# Main.net
KiCad netlist of a schematic drawn in EAGLE
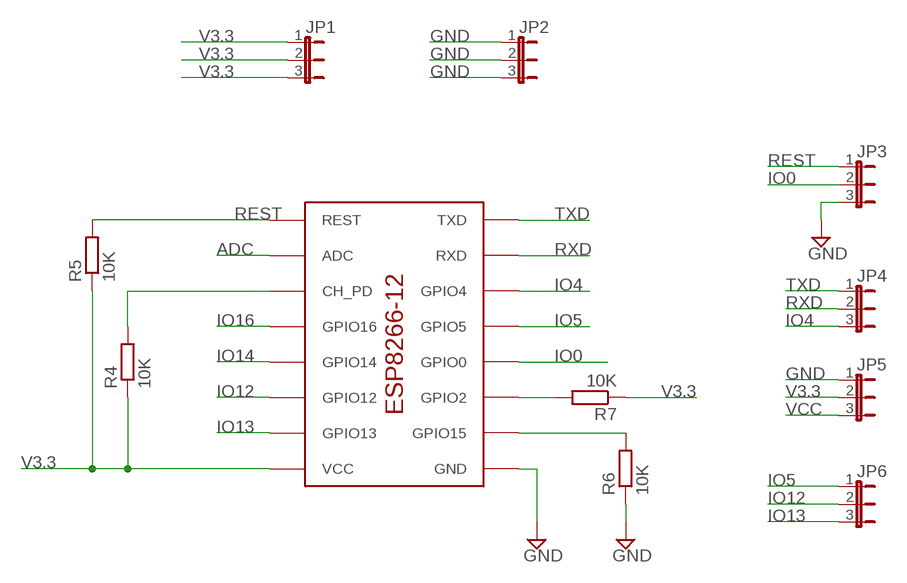
[diagram p0: schematic, sheet 1]

(export (version "E")
  (design (tool "Eeschema 10.0.6"))
  (components
    (comp (ref "JP1")
      (value "JP2E")
      (footprint "eagle-import:JP2")
      (libsource (lib "eagle-import") (part "JP2E"))
    )
    (comp (ref "JP2")
      (value "JP2E")
      (footprint "eagle-import:JP2")
      (libsource (lib "eagle-import") (part "JP2E"))
    )
    (comp (ref "JP3")
      (value "JP2E")
      (footprint "eagle-import:JP2")
      (libsource (lib "eagle-import") (part "JP2E"))
    )
    (comp (ref "JP4")
      (value "JP2E")
      (footprint "eagle-import:JP2")
      (libsource (lib "eagle-import") (part "JP2E"))
    )
    (comp (ref "JP5")
      (value "JP2E")
      (footprint "eagle-import:JP2")
      (libsource (lib "eagle-import") (part "JP2E"))
    )
    (comp (ref "JP6")
      (value "JP2E")
      (footprint "eagle-import:JP2")
      (libsource (lib "eagle-import") (part "JP2E"))
    )
    (comp (ref "R4")
      (value "10K")
      (footprint "eagle-import:M0805")
      (libsource (lib "eagle-import") (part "R-EU_M0805"))
    )
    (comp (ref "R5")
      (value "10K")
      (footprint "eagle-import:M0805")
      (libsource (lib "eagle-import") (part "R-EU_M0805"))
    )
    (comp (ref "R6")
      (value "10K")
      (footprint "eagle-import:M0805")
      (libsource (lib "eagle-import") (part "R-EU_M0805"))
    )
    (comp (ref "R7")
      (value "10K")
      (footprint "eagle-import:M0805")
      (libsource (lib "eagle-import") (part "R-EU_M0805"))
    )
    (comp (ref "U$1")
      (value "ESP8266-12")
      (footprint "eagle-import:ESP8266-12")
      (libsource (lib "eagle-import") (part "ESP8266-12"))
    )
  )
  (nets
    (net (code "1") (name "/ADC") (class "Default")
      (node (ref "U$1") (pin "ADC") (pinfunction "ADC_ADC") (pintype "bidirectional"))
    )
    (net (code "2") (name "/IO0") (class "Default")
      (node (ref "JP3") (pin "2") (pinfunction "2_2") (pintype "passive"))
      (node (ref "U$1") (pin "GPIO0") (pinfunction "GPIO0_GPIO0") (pintype "bidirectional"))
    )
    (net (code "3") (name "/IO4") (class "Default")
      (node (ref "JP4") (pin "3") (pinfunction "3_3") (pintype "passive"))
      (node (ref "U$1") (pin "GPIO4") (pinfunction "GPIO4_GPIO4") (pintype "bidirectional"))
    )
    (net (code "4") (name "/IO5") (class "Default")
      (node (ref "JP6") (pin "1") (pinfunction "1_1") (pintype "passive"))
      (node (ref "U$1") (pin "GPIO5") (pinfunction "GPIO5_GPIO5") (pintype "bidirectional"))
    )
    (net (code "5") (name "/IO12") (class "Default")
      (node (ref "JP6") (pin "2") (pinfunction "2_2") (pintype "passive"))
      (node (ref "U$1") (pin "GPIO12") (pinfunction "GPIO12_GPIO12") (pintype "bidirectional"))
    )
    (net (code "6") (name "/IO13") (class "Default")
      (node (ref "JP6") (pin "3") (pinfunction "3_3") (pintype "passive"))
      (node (ref "U$1") (pin "GPIO13") (pinfunction "GPIO13_GPIO13") (pintype "bidirectional"))
    )
    (net (code "7") (name "/IO14") (class "Default")
      (node (ref "U$1") (pin "GPIO14") (pinfunction "GPIO14_GPIO14") (pintype "bidirectional"))
    )
    (net (code "8") (name "/IO16") (class "Default")
      (node (ref "U$1") (pin "GPIO16") (pinfunction "GPIO16_GPIO16") (pintype "bidirectional"))
    )
    (net (code "9") (name "/REST") (class "Default")
      (node (ref "JP3") (pin "1") (pinfunction "1_1") (pintype "passive"))
      (node (ref "R5") (pin "2") (pinfunction "2_2") (pintype "passive"))
      (node (ref "U$1") (pin "REST") (pinfunction "REST_REST") (pintype "bidirectional"))
    )
    (net (code "10") (name "/RXD") (class "Default")
      (node (ref "JP4") (pin "2") (pinfunction "2_2") (pintype "passive"))
      (node (ref "U$1") (pin "RXD") (pinfunction "RXD_RXD") (pintype "bidirectional"))
    )
    (net (code "11") (name "/TXD") (class "Default")
      (node (ref "JP4") (pin "1") (pinfunction "1_1") (pintype "passive"))
      (node (ref "U$1") (pin "TXD") (pinfunction "TXD_TXD") (pintype "bidirectional"))
    )
    (net (code "12") (name "/V3.3") (class "Default")
      (node (ref "JP1") (pin "1") (pinfunction "1_1") (pintype "passive"))
      (node (ref "JP1") (pin "2") (pinfunction "2_2") (pintype "passive"))
      (node (ref "JP1") (pin "3") (pinfunction "3_3") (pintype "passive"))
      (node (ref "JP5") (pin "2") (pinfunction "2_2") (pintype "passive"))
      (node (ref "R4") (pin "1") (pinfunction "1_1") (pintype "passive"))
      (node (ref "R5") (pin "1") (pinfunction "1_1") (pintype "passive"))
      (node (ref "R7") (pin "1") (pinfunction "1_1") (pintype "passive"))
      (node (ref "U$1") (pin "VCC") (pinfunction "VCC_VCC") (pintype "bidirectional"))
    )
    (net (code "13") (name "/VCC") (class "Default")
      (node (ref "JP5") (pin "3") (pinfunction "3_3") (pintype "passive"))
    )
    (net (code "14") (name "GND") (class "Default")
      (node (ref "JP2") (pin "1") (pinfunction "1_1") (pintype "passive"))
      (node (ref "JP2") (pin "2") (pinfunction "2_2") (pintype "passive"))
      (node (ref "JP2") (pin "3") (pinfunction "3_3") (pintype "passive"))
      (node (ref "JP3") (pin "3") (pinfunction "3_3") (pintype "passive"))
      (node (ref "JP5") (pin "1") (pinfunction "1_1") (pintype "passive"))
      (node (ref "R6") (pin "1") (pinfunction "1_1") (pintype "passive"))
      (node (ref "U$1") (pin "GND") (pinfunction "GND_GND") (pintype "bidirectional"))
    )
    (net (code "15") (name "Net-(R4-Pad2)") (class "Default")
      (node (ref "R4") (pin "2") (pinfunction "2_2") (pintype "passive"))
      (node (ref "U$1") (pin "CH_PD") (pinfunction "CH_PD_CH_PD") (pintype "bidirectional"))
    )
    (net (code "16") (name "Net-(R6-Pad2)") (class "Default")
      (node (ref "R6") (pin "2") (pinfunction "2_2") (pintype "passive"))
      (node (ref "U$1") (pin "GPIO15") (pinfunction "GPIO15_GPIO15") (pintype "bidirectional"))
    )
    (net (code "17") (name "Net-(R7-Pad2)") (class "Default")
      (node (ref "R7") (pin "2") (pinfunction "2_2") (pintype "passive"))
      (node (ref "U$1") (pin "GPIO2") (pinfunction "GPIO2_GPIO2") (pintype "bidirectional"))
    )
  )
)
